# SHIFT_REG_LED_CONTROLLER_copy.net
KiCad netlist of a schematic drawn in EAGLE
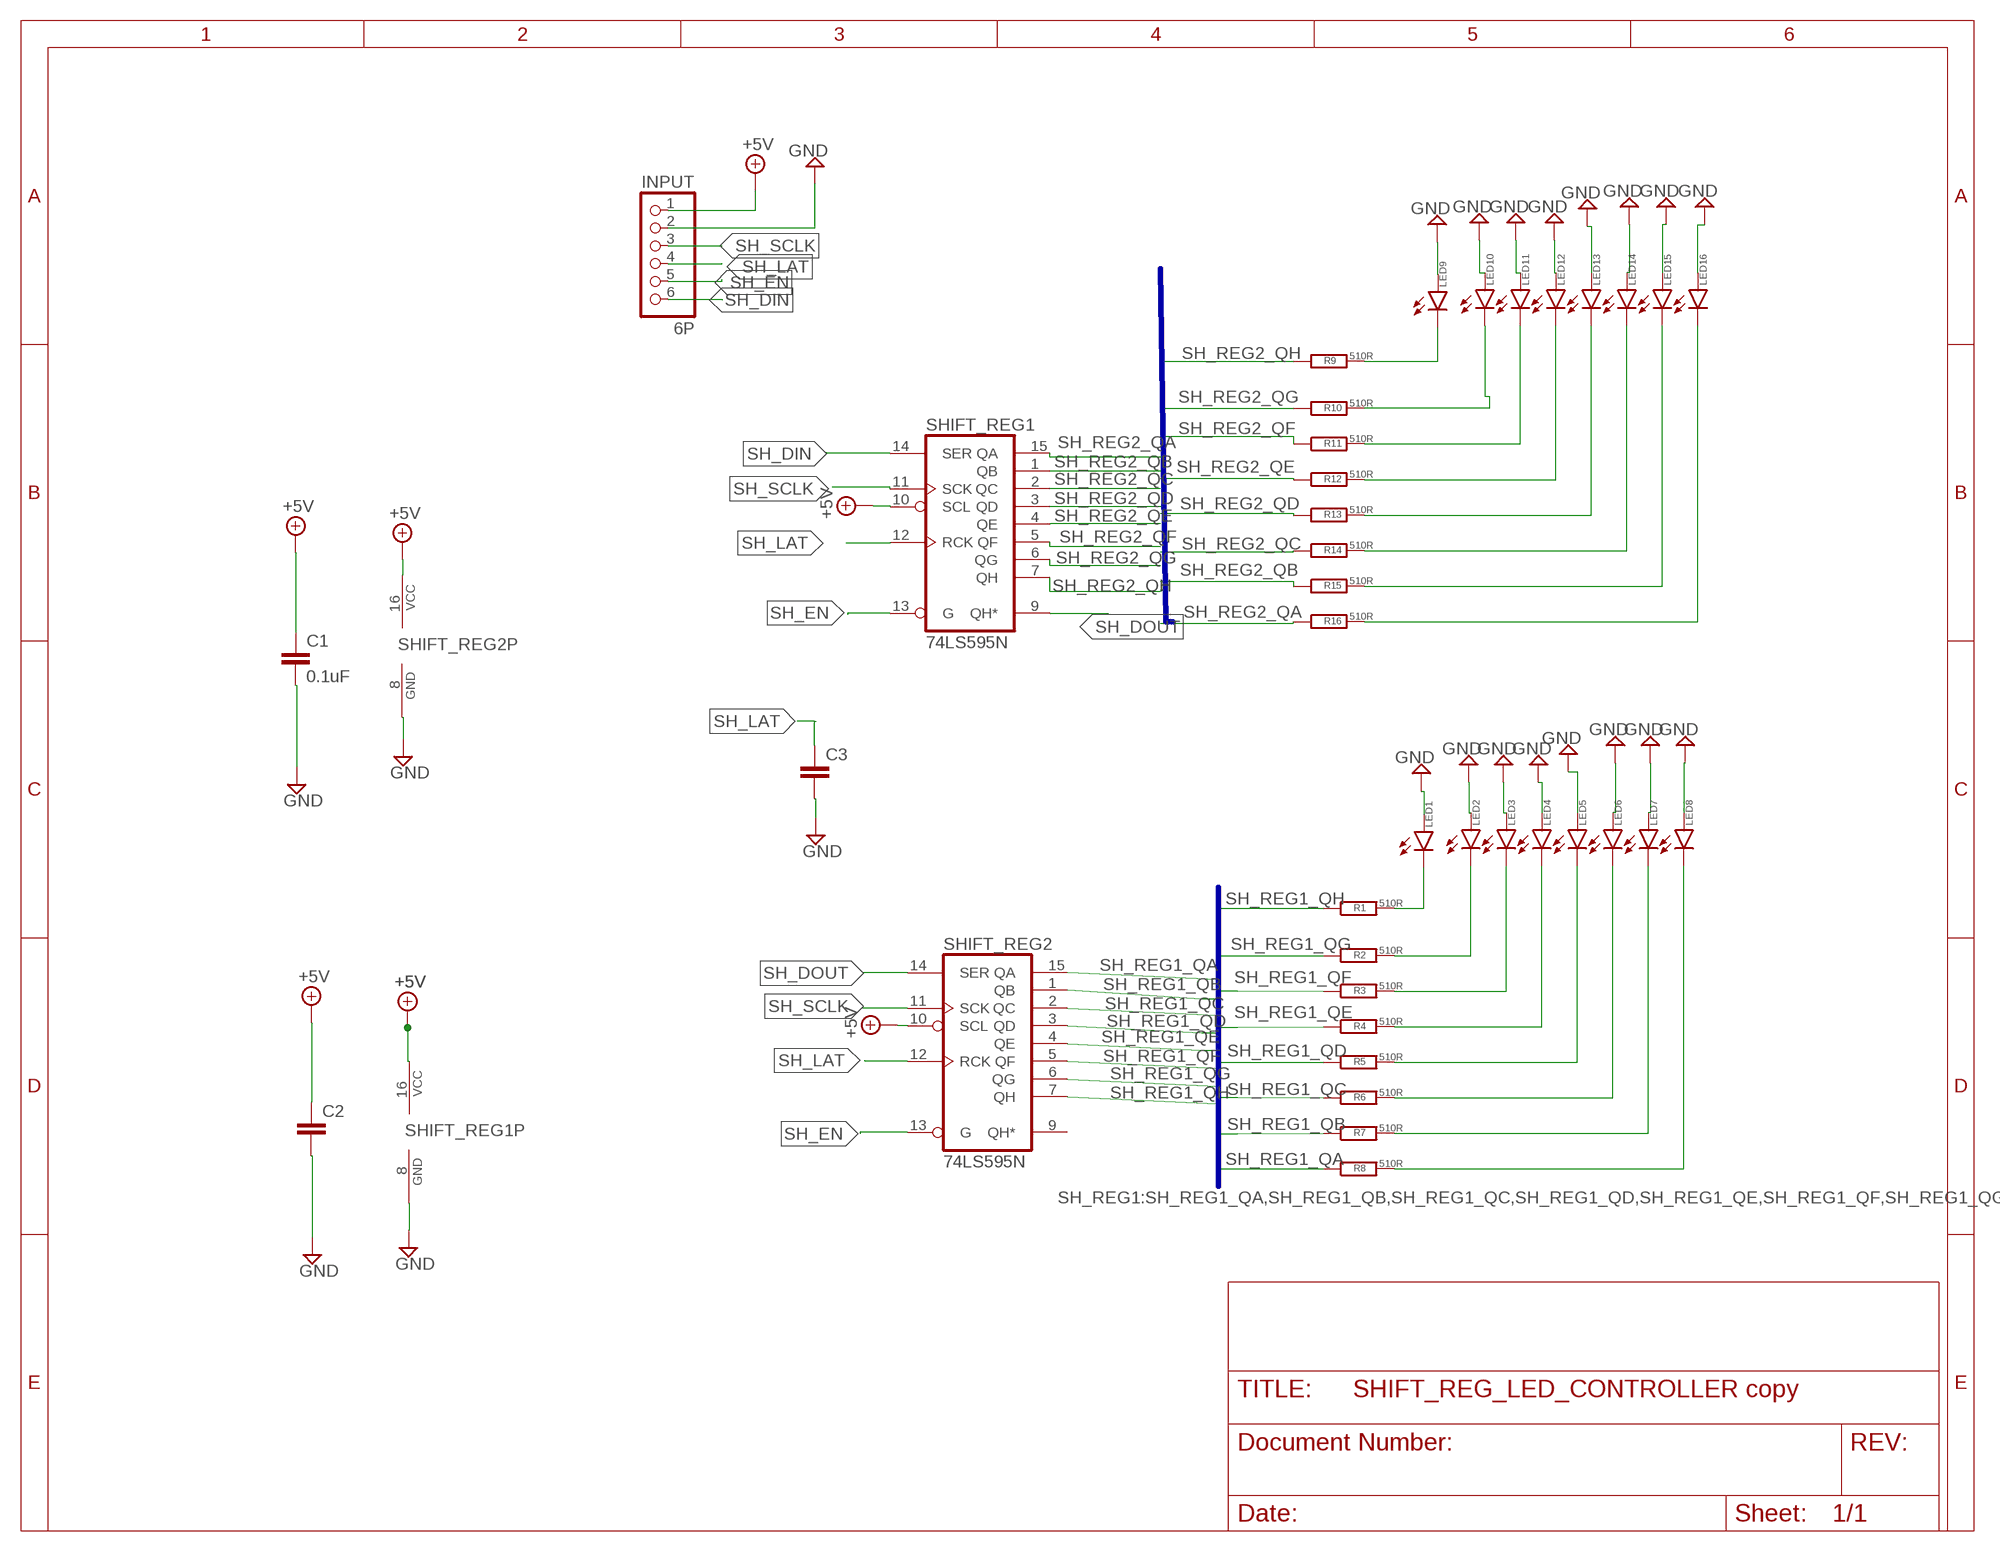
[diagram p0: schematic, sheet 1]

(export (version "E")
  (design (tool "Eeschema 10.0.6"))
  (components
    (comp (ref "C1")
      (value "0.1uF")
      (footprint "eagle-import:C050-030X075")
      (libsource (lib "eagle-import") (part "C-EU050-030X075"))
    )
    (comp (ref "C2")
      (value "C-EU050-030X075")
      (footprint "eagle-import:C050-030X075")
      (libsource (lib "eagle-import") (part "C-EU050-030X075"))
    )
    (comp (ref "C3")
      (value "C-EU050-030X075")
      (footprint "eagle-import:C050-030X075")
      (libsource (lib "eagle-import") (part "C-EU050-030X075"))
    )
    (comp (ref "INPUT")
      (value "6P")
      (footprint "eagle-import:1X06")
      (libsource (lib "eagle-import") (part "PINHD-1X6"))
    )
    (comp (ref "LED1")
      (value "LED5MM")
      (footprint "eagle-import:LED5MM")
      (libsource (lib "eagle-import") (part "LED5MM"))
    )
    (comp (ref "LED2")
      (value "LED5MM")
      (footprint "eagle-import:LED5MM")
      (libsource (lib "eagle-import") (part "LED5MM"))
    )
    (comp (ref "LED3")
      (value "LED5MM")
      (footprint "eagle-import:LED5MM")
      (libsource (lib "eagle-import") (part "LED5MM"))
    )
    (comp (ref "LED4")
      (value "LED5MM")
      (footprint "eagle-import:LED5MM")
      (libsource (lib "eagle-import") (part "LED5MM"))
    )
    (comp (ref "LED5")
      (value "LED5MM")
      (footprint "eagle-import:LED5MM")
      (libsource (lib "eagle-import") (part "LED5MM"))
    )
    (comp (ref "LED6")
      (value "LED5MM")
      (footprint "eagle-import:LED5MM")
      (libsource (lib "eagle-import") (part "LED5MM"))
    )
    (comp (ref "LED7")
      (value "LED5MM")
      (footprint "eagle-import:LED5MM")
      (libsource (lib "eagle-import") (part "LED5MM"))
    )
    (comp (ref "LED8")
      (value "LED5MM")
      (footprint "eagle-import:LED5MM")
      (libsource (lib "eagle-import") (part "LED5MM"))
    )
    (comp (ref "LED9")
      (value "LED5MM")
      (footprint "eagle-import:LED5MM")
      (libsource (lib "eagle-import") (part "LED5MM"))
    )
    (comp (ref "LED10")
      (value "LED5MM")
      (footprint "eagle-import:LED5MM")
      (libsource (lib "eagle-import") (part "LED5MM"))
    )
    (comp (ref "LED11")
      (value "LED5MM")
      (footprint "eagle-import:LED5MM")
      (libsource (lib "eagle-import") (part "LED5MM"))
    )
    (comp (ref "LED12")
      (value "LED5MM")
      (footprint "eagle-import:LED5MM")
      (libsource (lib "eagle-import") (part "LED5MM"))
    )
    (comp (ref "LED13")
      (value "LED5MM")
      (footprint "eagle-import:LED5MM")
      (libsource (lib "eagle-import") (part "LED5MM"))
    )
    (comp (ref "LED14")
      (value "LED5MM")
      (footprint "eagle-import:LED5MM")
      (libsource (lib "eagle-import") (part "LED5MM"))
    )
    (comp (ref "LED15")
      (value "LED5MM")
      (footprint "eagle-import:LED5MM")
      (libsource (lib "eagle-import") (part "LED5MM"))
    )
    (comp (ref "LED16")
      (value "LED5MM")
      (footprint "eagle-import:LED5MM")
      (libsource (lib "eagle-import") (part "LED5MM"))
    )
    (comp (ref "R1")
      (value "510R")
      (footprint "eagle-import:0207_10")
      (libsource (lib "eagle-import") (part "R-EU_0207/10"))
    )
    (comp (ref "R2")
      (value "510R")
      (footprint "eagle-import:0207_10")
      (libsource (lib "eagle-import") (part "R-EU_0207/10"))
    )
    (comp (ref "R3")
      (value "510R")
      (footprint "eagle-import:0207_10")
      (libsource (lib "eagle-import") (part "R-EU_0207/10"))
    )
    (comp (ref "R4")
      (value "510R")
      (footprint "eagle-import:0207_10")
      (libsource (lib "eagle-import") (part "R-EU_0207/10"))
    )
    (comp (ref "R5")
      (value "510R")
      (footprint "eagle-import:0207_10")
      (libsource (lib "eagle-import") (part "R-EU_0207/10"))
    )
    (comp (ref "R6")
      (value "510R")
      (footprint "eagle-import:0207_10")
      (libsource (lib "eagle-import") (part "R-EU_0207/10"))
    )
    (comp (ref "R7")
      (value "510R")
      (footprint "eagle-import:0207_10")
      (libsource (lib "eagle-import") (part "R-EU_0207/10"))
    )
    (comp (ref "R8")
      (value "510R")
      (footprint "eagle-import:0207_10")
      (libsource (lib "eagle-import") (part "R-EU_0207/10"))
    )
    (comp (ref "R9")
      (value "510R")
      (footprint "eagle-import:0207_10")
      (libsource (lib "eagle-import") (part "R-EU_0207/10"))
    )
    (comp (ref "R10")
      (value "510R")
      (footprint "eagle-import:0207_10")
      (libsource (lib "eagle-import") (part "R-EU_0207/10"))
    )
    (comp (ref "R11")
      (value "510R")
      (footprint "eagle-import:0207_10")
      (libsource (lib "eagle-import") (part "R-EU_0207/10"))
    )
    (comp (ref "R12")
      (value "510R")
      (footprint "eagle-import:0207_10")
      (libsource (lib "eagle-import") (part "R-EU_0207/10"))
    )
    (comp (ref "R13")
      (value "510R")
      (footprint "eagle-import:0207_10")
      (libsource (lib "eagle-import") (part "R-EU_0207/10"))
    )
    (comp (ref "R14")
      (value "510R")
      (footprint "eagle-import:0207_10")
      (libsource (lib "eagle-import") (part "R-EU_0207/10"))
    )
    (comp (ref "R15")
      (value "510R")
      (footprint "eagle-import:0207_10")
      (libsource (lib "eagle-import") (part "R-EU_0207/10"))
    )
    (comp (ref "R16")
      (value "510R")
      (footprint "eagle-import:0207_10")
      (libsource (lib "eagle-import") (part "R-EU_0207/10"))
    )
    (comp (ref "SHIFT_REG1")
      (value "74LS595N")
      (footprint "eagle-import:DIL16")
      (libsource (lib "eagle-import") (part "74595NLS"))
    )
    (comp (ref "SHIFT_REG2")
      (value "74LS595N")
      (footprint "eagle-import:DIL16")
      (libsource (lib "eagle-import") (part "74595NLS"))
    )
  )
  (nets
    (net (code "2") (name "+5V") (class "Default")
      (node (ref "C1") (pin "1") (pinfunction "1_1") (pintype "passive"))
      (node (ref "C2") (pin "1") (pinfunction "1_1") (pintype "passive"))
      (node (ref "INPUT") (pin "1") (pinfunction "1_1") (pintype "passive"))
      (node (ref "SHIFT_REG1") (pin "10") (pinfunction "SCL_10") (pintype "input"))
      (node (ref "SHIFT_REG1") (pin "16") (pinfunction "VCC_16") (pintype "power_in"))
      (node (ref "SHIFT_REG2") (pin "10") (pinfunction "SCL_10") (pintype "input"))
      (node (ref "SHIFT_REG2") (pin "16") (pinfunction "VCC_16") (pintype "power_in"))
    )
    (net (code "3") (name "/SH_REG1_QA") (class "Default")
      (node (ref "R8") (pin "1") (pinfunction "1_1") (pintype "passive"))
      (node (ref "SHIFT_REG2") (pin "15") (pinfunction "QA_15") (pintype "tri_state"))
    )
    (net (code "4") (name "/SH_REG1_QB") (class "Default")
      (node (ref "R7") (pin "1") (pinfunction "1_1") (pintype "passive"))
      (node (ref "SHIFT_REG2") (pin "1") (pinfunction "QB_1") (pintype "tri_state"))
    )
    (net (code "5") (name "/SH_REG1_QC") (class "Default")
      (node (ref "R6") (pin "1") (pinfunction "1_1") (pintype "passive"))
      (node (ref "SHIFT_REG2") (pin "2") (pinfunction "QC_2") (pintype "tri_state"))
    )
    (net (code "6") (name "/SH_REG1_QD") (class "Default")
      (node (ref "R5") (pin "1") (pinfunction "1_1") (pintype "passive"))
      (node (ref "SHIFT_REG2") (pin "3") (pinfunction "QD_3") (pintype "tri_state"))
    )
    (net (code "7") (name "/SH_REG1_QE") (class "Default")
      (node (ref "R4") (pin "1") (pinfunction "1_1") (pintype "passive"))
      (node (ref "SHIFT_REG2") (pin "4") (pinfunction "QE_4") (pintype "tri_state"))
    )
    (net (code "8") (name "/SH_REG1_QF") (class "Default")
      (node (ref "R3") (pin "1") (pinfunction "1_1") (pintype "passive"))
      (node (ref "SHIFT_REG2") (pin "5") (pinfunction "QF_5") (pintype "tri_state"))
    )
    (net (code "9") (name "/SH_REG1_QG") (class "Default")
      (node (ref "R2") (pin "1") (pinfunction "1_1") (pintype "passive"))
      (node (ref "SHIFT_REG2") (pin "6") (pinfunction "QG_6") (pintype "tri_state"))
    )
    (net (code "10") (name "/SH_REG1_QH") (class "Default")
      (node (ref "R1") (pin "1") (pinfunction "1_1") (pintype "passive"))
      (node (ref "SHIFT_REG2") (pin "7") (pinfunction "QH_7") (pintype "tri_state"))
    )
    (net (code "11") (name "/SH_REG2_QA") (class "Default")
      (node (ref "R16") (pin "1") (pinfunction "1_1") (pintype "passive"))
      (node (ref "SHIFT_REG1") (pin "15") (pinfunction "QA_15") (pintype "tri_state"))
    )
    (net (code "12") (name "/SH_REG2_QB") (class "Default")
      (node (ref "R15") (pin "1") (pinfunction "1_1") (pintype "passive"))
      (node (ref "SHIFT_REG1") (pin "1") (pinfunction "QB_1") (pintype "tri_state"))
    )
    (net (code "13") (name "/SH_REG2_QC") (class "Default")
      (node (ref "R14") (pin "1") (pinfunction "1_1") (pintype "passive"))
      (node (ref "SHIFT_REG1") (pin "2") (pinfunction "QC_2") (pintype "tri_state"))
    )
    (net (code "14") (name "/SH_REG2_QD") (class "Default")
      (node (ref "R13") (pin "1") (pinfunction "1_1") (pintype "passive"))
      (node (ref "SHIFT_REG1") (pin "3") (pinfunction "QD_3") (pintype "tri_state"))
    )
    (net (code "15") (name "/SH_REG2_QE") (class "Default")
      (node (ref "R12") (pin "1") (pinfunction "1_1") (pintype "passive"))
      (node (ref "SHIFT_REG1") (pin "4") (pinfunction "QE_4") (pintype "tri_state"))
    )
    (net (code "16") (name "/SH_REG2_QF") (class "Default")
      (node (ref "R11") (pin "1") (pinfunction "1_1") (pintype "passive"))
      (node (ref "SHIFT_REG1") (pin "5") (pinfunction "QF_5") (pintype "tri_state"))
    )
    (net (code "17") (name "/SH_REG2_QG") (class "Default")
      (node (ref "R10") (pin "1") (pinfunction "1_1") (pintype "passive"))
      (node (ref "SHIFT_REG1") (pin "6") (pinfunction "QG_6") (pintype "tri_state"))
    )
    (net (code "18") (name "/SH_REG2_QH") (class "Default")
      (node (ref "R9") (pin "1") (pinfunction "1_1") (pintype "passive"))
      (node (ref "SHIFT_REG1") (pin "7") (pinfunction "QH_7") (pintype "tri_state"))
    )
    (net (code "20") (name "GND") (class "Default")
      (node (ref "C1") (pin "2") (pinfunction "2_2") (pintype "passive"))
      (node (ref "C2") (pin "2") (pinfunction "2_2") (pintype "passive"))
      (node (ref "C3") (pin "2") (pinfunction "2_2") (pintype "passive"))
      (node (ref "INPUT") (pin "2") (pinfunction "2_2") (pintype "passive"))
      (node (ref "LED1") (pin "A") (pinfunction "A_A") (pintype "passive"))
      (node (ref "LED10") (pin "A") (pinfunction "A_A") (pintype "passive"))
      (node (ref "LED11") (pin "A") (pinfunction "A_A") (pintype "passive"))
      (node (ref "LED12") (pin "A") (pinfunction "A_A") (pintype "passive"))
      (node (ref "LED13") (pin "A") (pinfunction "A_A") (pintype "passive"))
      (node (ref "LED14") (pin "A") (pinfunction "A_A") (pintype "passive"))
      (node (ref "LED15") (pin "A") (pinfunction "A_A") (pintype "passive"))
      (node (ref "LED16") (pin "A") (pinfunction "A_A") (pintype "passive"))
      (node (ref "LED2") (pin "A") (pinfunction "A_A") (pintype "passive"))
      (node (ref "LED3") (pin "A") (pinfunction "A_A") (pintype "passive"))
      (node (ref "LED4") (pin "A") (pinfunction "A_A") (pintype "passive"))
      (node (ref "LED5") (pin "A") (pinfunction "A_A") (pintype "passive"))
      (node (ref "LED6") (pin "A") (pinfunction "A_A") (pintype "passive"))
      (node (ref "LED7") (pin "A") (pinfunction "A_A") (pintype "passive"))
      (node (ref "LED8") (pin "A") (pinfunction "A_A") (pintype "passive"))
      (node (ref "LED9") (pin "A") (pinfunction "A_A") (pintype "passive"))
      (node (ref "SHIFT_REG1") (pin "8") (pinfunction "GND_8") (pintype "power_in"))
      (node (ref "SHIFT_REG2") (pin "8") (pinfunction "GND_8") (pintype "power_in"))
    )
    (net (code "21") (name "Net-(LED1-C)") (class "Default")
      (node (ref "LED1") (pin "K") (pinfunction "C_K") (pintype "passive"))
      (node (ref "R1") (pin "2") (pinfunction "2_2") (pintype "passive"))
    )
    (net (code "22") (name "Net-(LED2-C)") (class "Default")
      (node (ref "LED2") (pin "K") (pinfunction "C_K") (pintype "passive"))
      (node (ref "R2") (pin "2") (pinfunction "2_2") (pintype "passive"))
    )
    (net (code "23") (name "Net-(LED3-C)") (class "Default")
      (node (ref "LED3") (pin "K") (pinfunction "C_K") (pintype "passive"))
      (node (ref "R3") (pin "2") (pinfunction "2_2") (pintype "passive"))
    )
    (net (code "24") (name "Net-(LED4-C)") (class "Default")
      (node (ref "LED4") (pin "K") (pinfunction "C_K") (pintype "passive"))
      (node (ref "R4") (pin "2") (pinfunction "2_2") (pintype "passive"))
    )
    (net (code "25") (name "Net-(LED5-C)") (class "Default")
      (node (ref "LED5") (pin "K") (pinfunction "C_K") (pintype "passive"))
      (node (ref "R5") (pin "2") (pinfunction "2_2") (pintype "passive"))
    )
    (net (code "26") (name "Net-(LED6-C)") (class "Default")
      (node (ref "LED6") (pin "K") (pinfunction "C_K") (pintype "passive"))
      (node (ref "R6") (pin "2") (pinfunction "2_2") (pintype "passive"))
    )
    (net (code "27") (name "Net-(LED7-C)") (class "Default")
      (node (ref "LED7") (pin "K") (pinfunction "C_K") (pintype "passive"))
      (node (ref "R7") (pin "2") (pinfunction "2_2") (pintype "passive"))
    )
    (net (code "28") (name "Net-(LED8-C)") (class "Default")
      (node (ref "LED8") (pin "K") (pinfunction "C_K") (pintype "passive"))
      (node (ref "R8") (pin "2") (pinfunction "2_2") (pintype "passive"))
    )
    (net (code "29") (name "Net-(LED9-C)") (class "Default")
      (node (ref "LED9") (pin "K") (pinfunction "C_K") (pintype "passive"))
      (node (ref "R9") (pin "2") (pinfunction "2_2") (pintype "passive"))
    )
    (net (code "30") (name "Net-(LED10-C)") (class "Default")
      (node (ref "LED10") (pin "K") (pinfunction "C_K") (pintype "passive"))
      (node (ref "R10") (pin "2") (pinfunction "2_2") (pintype "passive"))
    )
    (net (code "31") (name "Net-(LED11-C)") (class "Default")
      (node (ref "LED11") (pin "K") (pinfunction "C_K") (pintype "passive"))
      (node (ref "R11") (pin "2") (pinfunction "2_2") (pintype "passive"))
    )
    (net (code "32") (name "Net-(LED12-C)") (class "Default")
      (node (ref "LED12") (pin "K") (pinfunction "C_K") (pintype "passive"))
      (node (ref "R12") (pin "2") (pinfunction "2_2") (pintype "passive"))
    )
    (net (code "33") (name "Net-(LED13-C)") (class "Default")
      (node (ref "LED13") (pin "K") (pinfunction "C_K") (pintype "passive"))
      (node (ref "R13") (pin "2") (pinfunction "2_2") (pintype "passive"))
    )
    (net (code "34") (name "Net-(LED14-C)") (class "Default")
      (node (ref "LED14") (pin "K") (pinfunction "C_K") (pintype "passive"))
      (node (ref "R14") (pin "2") (pinfunction "2_2") (pintype "passive"))
    )
    (net (code "35") (name "Net-(LED15-C)") (class "Default")
      (node (ref "LED15") (pin "K") (pinfunction "C_K") (pintype "passive"))
      (node (ref "R15") (pin "2") (pinfunction "2_2") (pintype "passive"))
    )
    (net (code "36") (name "Net-(LED16-C)") (class "Default")
      (node (ref "LED16") (pin "K") (pinfunction "C_K") (pintype "passive"))
      (node (ref "R16") (pin "2") (pinfunction "2_2") (pintype "passive"))
    )
    (net (code "37") (name "SH_DIN") (class "Default")
      (node (ref "INPUT") (pin "6") (pinfunction "6_6") (pintype "passive"))
      (node (ref "SHIFT_REG1") (pin "14") (pinfunction "SER_14") (pintype "input"))
    )
    (net (code "38") (name "SH_DOUT") (class "Default")
      (node (ref "SHIFT_REG1") (pin "9") (pinfunction "QH*_9") (pintype "tri_state"))
      (node (ref "SHIFT_REG2") (pin "14") (pinfunction "SER_14") (pintype "input"))
    )
    (net (code "39") (name "SH_EN") (class "Default")
      (node (ref "INPUT") (pin "5") (pinfunction "5_5") (pintype "passive"))
      (node (ref "SHIFT_REG1") (pin "13") (pinfunction "G_13") (pintype "input"))
      (node (ref "SHIFT_REG2") (pin "13") (pinfunction "G_13") (pintype "input"))
    )
    (net (code "40") (name "SH_LAT") (class "Default")
      (node (ref "C3") (pin "1") (pinfunction "1_1") (pintype "passive"))
      (node (ref "INPUT") (pin "4") (pinfunction "4_4") (pintype "passive"))
      (node (ref "SHIFT_REG1") (pin "12") (pinfunction "RCK_12") (pintype "input"))
      (node (ref "SHIFT_REG2") (pin "12") (pinfunction "RCK_12") (pintype "input"))
    )
    (net (code "41") (name "SH_SCLK") (class "Default")
      (node (ref "INPUT") (pin "3") (pinfunction "3_3") (pintype "passive"))
      (node (ref "SHIFT_REG1") (pin "11") (pinfunction "SCK_11") (pintype "input"))
      (node (ref "SHIFT_REG2") (pin "11") (pinfunction "SCK_11") (pintype "input"))
    )
    (net (code "42") (name "unconnected-(SHIFT_REG2A-QH*-Pad9)") (class "Default")
      (node (ref "SHIFT_REG2") (pin "9") (pinfunction "QH*_9") (pintype "tri_state"))
    )
  )
)
